# AHRS_Sch.net
KiCad netlist of a schematic drawn in Altium Designer
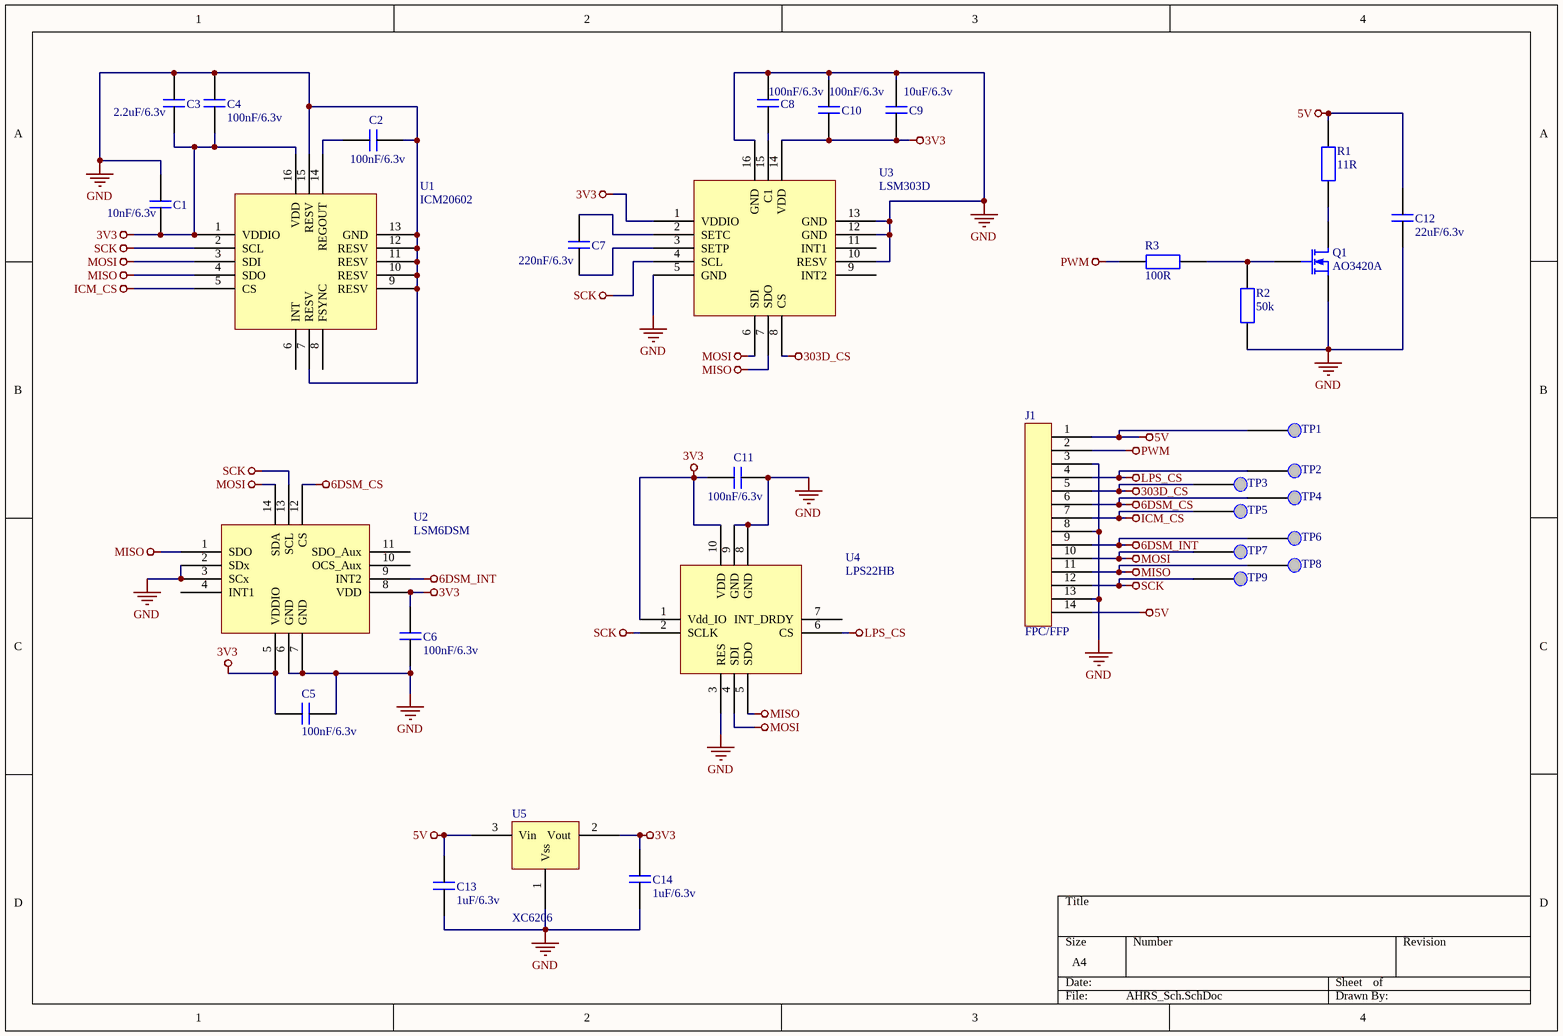
[diagram p0: AHRS_Sch.SchDoc]

(export (version "E")
  (design (tool "Eeschema 10.0.6"))
  (components
    (comp (ref "C1")
      (value "10nF/6.3v")
      (footprint "C_0603")
      (description "Capacitence")
      (libsource (lib "AHRS") (part "Capacitence"))
    )
    (comp (ref "C2")
      (value "100nF/6.3v")
      (footprint "C_0603")
      (description "Capacitence")
      (libsource (lib "AHRS") (part "Capacitence"))
    )
    (comp (ref "C3")
      (value "2.2uF/6.3v")
      (footprint "C_0603")
      (description "Capacitence")
      (libsource (lib "AHRS") (part "Capacitence"))
    )
    (comp (ref "C4")
      (value "100nF/6.3v")
      (footprint "C_0603")
      (description "Capacitence")
      (libsource (lib "AHRS") (part "Capacitence"))
    )
    (comp (ref "C5")
      (value "100nF/6.3v")
      (footprint "C_0603")
      (description "Capacitence")
      (libsource (lib "AHRS") (part "Capacitence"))
    )
    (comp (ref "C6")
      (value "100nF/6.3v")
      (footprint "C_0603")
      (description "Capacitence")
      (libsource (lib "AHRS") (part "Capacitence"))
    )
    (comp (ref "C7")
      (value "220nF/6.3v")
      (footprint "C_0603")
      (description "Capacitence")
      (libsource (lib "AHRS") (part "Capacitence"))
    )
    (comp (ref "C8")
      (value "100nF/6.3v")
      (footprint "C_0603")
      (description "Capacitence")
      (libsource (lib "AHRS") (part "Capacitence"))
    )
    (comp (ref "C9")
      (value "10uF/6.3v")
      (footprint "C_0603")
      (description "Capacitence")
      (libsource (lib "AHRS") (part "Capacitence"))
    )
    (comp (ref "C10")
      (value "100nF/6.3v")
      (footprint "C_0603")
      (description "Capacitence")
      (libsource (lib "AHRS") (part "Capacitence"))
    )
    (comp (ref "C11")
      (value "100nF/6.3v")
      (footprint "C_0603")
      (description "Capacitence")
      (libsource (lib "AHRS") (part "Capacitence"))
    )
    (comp (ref "C12")
      (value "22uF/6.3v")
      (footprint "C_0805")
      (description "Capacitence")
      (libsource (lib "AHRS") (part "Capacitence"))
    )
    (comp (ref "C13")
      (value "1uF/6.3v")
      (footprint "C_0603")
      (description "Capacitence")
      (libsource (lib "AHRS") (part "Capacitence"))
    )
    (comp (ref "C14")
      (value "1uF/6.3v")
      (footprint "C_0603")
      (description "Capacitence")
      (libsource (lib "AHRS") (part "Capacitence"))
    )
    (comp (ref "J1")
      (value "FPC/FFP")
      (footprint "FPC/FFP")
      (description "Connector")
      (libsource (lib "AHRS") (part "FPC/FFP"))
    )
    (comp (ref "Q1")
      (value "AO3420A")
      (footprint "SOT-23")
      (description "MOSFET")
      (libsource (lib "AHRS") (part "AO3420A"))
    )
    (comp (ref "R1")
      (value "11R")
      (footprint "R_2512")
      (description "Resistence")
      (libsource (lib "AHRS") (part "Resistence"))
    )
    (comp (ref "R2")
      (value "50k")
      (footprint "R_0603")
      (description "Resistence")
      (libsource (lib "AHRS") (part "Resistence"))
    )
    (comp (ref "R3")
      (value "100R")
      (footprint "R_0603")
      (description "Resistence")
      (libsource (lib "AHRS") (part "Resistence"))
    )
    (comp (ref "TP1") (value "~") (footprint "Test_Point") (libsource (lib "AHRS") (part "Testpoint")))
    (comp (ref "TP2") (value "~") (footprint "Test_Point") (libsource (lib "AHRS") (part "Testpoint")))
    (comp (ref "TP3") (value "~") (footprint "Test_Point") (libsource (lib "AHRS") (part "Testpoint")))
    (comp (ref "TP4") (value "~") (footprint "Test_Point") (libsource (lib "AHRS") (part "Testpoint")))
    (comp (ref "TP5") (value "~") (footprint "Test_Point") (libsource (lib "AHRS") (part "Testpoint")))
    (comp (ref "TP6") (value "~") (footprint "Test_Point") (libsource (lib "AHRS") (part "Testpoint")))
    (comp (ref "TP7") (value "~") (footprint "Test_Point") (libsource (lib "AHRS") (part "Testpoint")))
    (comp (ref "TP8") (value "~") (footprint "Test_Point") (libsource (lib "AHRS") (part "Testpoint")))
    (comp (ref "TP9") (value "~") (footprint "Test_Point") (libsource (lib "AHRS") (part "Testpoint")))
    (comp (ref "U1")
      (value "ICM20602")
      (footprint "LGA-16")
      (description "IMU")
      (libsource (lib "AHRS") (part "ICM20602"))
    )
    (comp (ref "U2")
      (value "LSM6DSM")
      (footprint "LGA-14L")
      (description "IMU")
      (libsource (lib "AHRS") (part "LSM6DSM"))
    )
    (comp (ref "U3")
      (value "LSM303D")
      (footprint "LGA-16")
      (description "Accelerometer & Compass")
      (libsource (lib "AHRS") (part "LSM303D"))
    )
    (comp (ref "U4")
      (value "LPS22HB")
      (footprint "HLGA-10L")
      (description "Barometer")
      (libsource (lib "AHRS") (part "LPS22HB"))
    )
    (comp (ref "U5")
      (value "XC6206")
      (footprint "SOT-23")
      (description "LDO")
      (libsource (lib "AHRS") (part "XC6206P332"))
    )
  )
  (nets
    (net (code "1") (name "3V3") (class "Default")
      (node (ref "C1") (pin "2") (pinfunction "2_2") (pintype "passive"))
      (node (ref "C10") (pin "1") (pinfunction "1_1") (pintype "passive"))
      (node (ref "C11") (pin "2") (pinfunction "2_2") (pintype "passive"))
      (node (ref "C14") (pin "2") (pinfunction "2_2") (pintype "passive"))
      (node (ref "C3") (pin "2") (pinfunction "2_2") (pintype "passive"))
      (node (ref "C4") (pin "1") (pinfunction "1_1") (pintype "passive"))
      (node (ref "C5") (pin "2") (pinfunction "2_2") (pintype "passive"))
      (node (ref "C6") (pin "2") (pinfunction "2_2") (pintype "passive"))
      (node (ref "C9") (pin "1") (pinfunction "1_1") (pintype "passive"))
      (node (ref "U1") (pin "1") (pinfunction "VDDIO_1") (pintype "passive"))
      (node (ref "U1") (pin "16") (pinfunction "VDD_16") (pintype "passive"))
      (node (ref "U2") (pin "5") (pinfunction "VDDIO_5") (pintype "passive"))
      (node (ref "U2") (pin "8") (pinfunction "VDD_8") (pintype "passive"))
      (node (ref "U3") (pin "1") (pinfunction "VDDIO_1") (pintype "passive"))
      (node (ref "U3") (pin "14") (pinfunction "VDD_14") (pintype "passive"))
      (node (ref "U4") (pin "1") (pinfunction "Vdd_IO_1") (pintype "passive"))
      (node (ref "U4") (pin "10") (pinfunction "VDD_10") (pintype "passive"))
      (node (ref "U5") (pin "2") (pinfunction "Vout_2") (pintype "passive"))
    )
    (net (code "2") (name "5V") (class "Default")
      (node (ref "C12") (pin "2") (pinfunction "2_2") (pintype "passive"))
      (node (ref "C13") (pin "2") (pinfunction "2_2") (pintype "passive"))
      (node (ref "J1") (pin "1") (pintype "passive"))
      (node (ref "J1") (pin "14") (pintype "passive"))
      (node (ref "R1") (pin "1") (pinfunction "1_1") (pintype "passive"))
      (node (ref "TP1") (pin "1") (pinfunction "1_1") (pintype "passive"))
      (node (ref "U5") (pin "3") (pinfunction "Vin_3") (pintype "passive"))
    )
    (net (code "3") (name "6DSM_CS") (class "Default")
      (node (ref "J1") (pin "6") (pintype "passive"))
      (node (ref "TP4") (pin "1") (pinfunction "1_1") (pintype "passive"))
      (node (ref "U2") (pin "12") (pinfunction "CS_12") (pintype "passive"))
    )
    (net (code "4") (name "6DSM_INT") (class "Default")
      (node (ref "J1") (pin "9") (pintype "passive"))
      (node (ref "TP6") (pin "1") (pinfunction "1_1") (pintype "passive"))
      (node (ref "U2") (pin "9") (pinfunction "INT2_9") (pintype "passive"))
    )
    (net (code "5") (name "303D_CS") (class "Default")
      (node (ref "J1") (pin "5") (pintype "passive"))
      (node (ref "TP3") (pin "1") (pinfunction "1_1") (pintype "passive"))
      (node (ref "U3") (pin "8") (pinfunction "CS_8") (pintype "passive"))
    )
    (net (code "6") (name "GND") (class "Default")
      (node (ref "C1") (pin "1") (pinfunction "1_1") (pintype "passive"))
      (node (ref "C10") (pin "2") (pinfunction "2_2") (pintype "passive"))
      (node (ref "C11") (pin "1") (pinfunction "1_1") (pintype "passive"))
      (node (ref "C12") (pin "1") (pinfunction "1_1") (pintype "passive"))
      (node (ref "C13") (pin "1") (pinfunction "1_1") (pintype "passive"))
      (node (ref "C14") (pin "1") (pinfunction "1_1") (pintype "passive"))
      (node (ref "C2") (pin "1") (pinfunction "1_1") (pintype "passive"))
      (node (ref "C3") (pin "1") (pinfunction "1_1") (pintype "passive"))
      (node (ref "C4") (pin "2") (pinfunction "2_2") (pintype "passive"))
      (node (ref "C5") (pin "1") (pinfunction "1_1") (pintype "passive"))
      (node (ref "C6") (pin "1") (pinfunction "1_1") (pintype "passive"))
      (node (ref "C8") (pin "1") (pinfunction "1_1") (pintype "passive"))
      (node (ref "C9") (pin "2") (pinfunction "2_2") (pintype "passive"))
      (node (ref "J1") (pin "13") (pintype "passive"))
      (node (ref "J1") (pin "3") (pintype "passive"))
      (node (ref "J1") (pin "8") (pintype "passive"))
      (node (ref "Q1") (pin "3") (pinfunction "S_3") (pintype "passive"))
      (node (ref "R2") (pin "1") (pinfunction "1_1") (pintype "passive"))
      (node (ref "U1") (pin "10") (pinfunction "RESV_10") (pintype "passive"))
      (node (ref "U1") (pin "11") (pinfunction "RESV_11") (pintype "passive"))
      (node (ref "U1") (pin "12") (pinfunction "RESV_12") (pintype "passive"))
      (node (ref "U1") (pin "13") (pinfunction "GND_13") (pintype "passive"))
      (node (ref "U1") (pin "15") (pinfunction "RESV_15") (pintype "passive"))
      (node (ref "U1") (pin "7") (pinfunction "RESV_7") (pintype "passive"))
      (node (ref "U1") (pin "9") (pinfunction "RESV_9") (pintype "passive"))
      (node (ref "U2") (pin "2") (pinfunction "SDx_2") (pintype "passive"))
      (node (ref "U2") (pin "3") (pinfunction "SCx_3") (pintype "passive"))
      (node (ref "U2") (pin "6") (pinfunction "GND_6") (pintype "passive"))
      (node (ref "U2") (pin "7") (pinfunction "GND_7") (pintype "passive"))
      (node (ref "U3") (pin "10") (pinfunction "RESV_10") (pintype "passive"))
      (node (ref "U3") (pin "12") (pinfunction "GND_12") (pintype "passive"))
      (node (ref "U3") (pin "13") (pinfunction "GND_13") (pintype "passive"))
      (node (ref "U3") (pin "16") (pinfunction "GND_16") (pintype "passive"))
      (node (ref "U3") (pin "5") (pinfunction "GND_5") (pintype "passive"))
      (node (ref "U4") (pin "3") (pinfunction "RES_3") (pintype "passive"))
      (node (ref "U4") (pin "8") (pinfunction "GND_8") (pintype "passive"))
      (node (ref "U4") (pin "9") (pinfunction "GND_9") (pintype "passive"))
      (node (ref "U5") (pin "1") (pinfunction "Vss_1") (pintype "passive"))
    )
    (net (code "7") (name "ICM_CS") (class "Default")
      (node (ref "J1") (pin "7") (pintype "passive"))
      (node (ref "TP5") (pin "1") (pinfunction "1_1") (pintype "passive"))
      (node (ref "U1") (pin "5") (pinfunction "CS_5") (pintype "passive"))
    )
    (net (code "8") (name "LPS_CS") (class "Default")
      (node (ref "J1") (pin "4") (pintype "passive"))
      (node (ref "TP2") (pin "1") (pinfunction "1_1") (pintype "passive"))
      (node (ref "U4") (pin "6") (pinfunction "CS_6") (pintype "passive"))
    )
    (net (code "9") (name "MISO") (class "Default")
      (node (ref "J1") (pin "11") (pintype "passive"))
      (node (ref "TP8") (pin "1") (pinfunction "1_1") (pintype "passive"))
      (node (ref "U1") (pin "4") (pinfunction "SDO_4") (pintype "passive"))
      (node (ref "U2") (pin "1") (pinfunction "SDO_1") (pintype "passive"))
      (node (ref "U3") (pin "7") (pinfunction "SDO_7") (pintype "passive"))
      (node (ref "U4") (pin "5") (pinfunction "SDO_5") (pintype "passive"))
    )
    (net (code "10") (name "MOSI") (class "Default")
      (node (ref "J1") (pin "10") (pintype "passive"))
      (node (ref "TP7") (pin "1") (pinfunction "1_1") (pintype "passive"))
      (node (ref "U1") (pin "3") (pinfunction "SDI_3") (pintype "passive"))
      (node (ref "U2") (pin "14") (pinfunction "SDA_14") (pintype "passive"))
      (node (ref "U3") (pin "6") (pinfunction "SDI_6") (pintype "passive"))
      (node (ref "U4") (pin "4") (pinfunction "SDI_4") (pintype "passive"))
    )
    (net (code "11") (name "Net-(Q1-D)") (class "Default")
      (node (ref "Q1") (pin "2") (pinfunction "D_2") (pintype "passive"))
      (node (ref "R1") (pin "2") (pinfunction "2_2") (pintype "passive"))
    )
    (net (code "12") (name "Net-(Q1-G)") (class "Default")
      (node (ref "Q1") (pin "1") (pinfunction "G_1") (pintype "passive"))
      (node (ref "R2") (pin "2") (pinfunction "2_2") (pintype "passive"))
      (node (ref "R3") (pin "2") (pinfunction "2_2") (pintype "passive"))
    )
    (net (code "13") (name "Net-(U1-REGOUT)") (class "Default")
      (node (ref "C2") (pin "2") (pinfunction "2_2") (pintype "passive"))
      (node (ref "U1") (pin "14") (pinfunction "REGOUT_14") (pintype "passive"))
    )
    (net (code "14") (name "Net-(U3-C1)") (class "Default")
      (node (ref "C8") (pin "2") (pinfunction "2_2") (pintype "passive"))
      (node (ref "U3") (pin "15") (pinfunction "C1_15") (pintype "passive"))
    )
    (net (code "15") (name "Net-(U3-SETC)") (class "Default")
      (node (ref "C7") (pin "1") (pinfunction "1_1") (pintype "passive"))
      (node (ref "U3") (pin "2") (pinfunction "SETC_2") (pintype "passive"))
    )
    (net (code "16") (name "Net-(U3-SETP)") (class "Default")
      (node (ref "C7") (pin "2") (pinfunction "2_2") (pintype "passive"))
      (node (ref "U3") (pin "3") (pinfunction "SETP_3") (pintype "passive"))
    )
    (net (code "17") (name "PWM") (class "Default")
      (node (ref "J1") (pin "2") (pintype "passive"))
      (node (ref "R3") (pin "1") (pinfunction "1_1") (pintype "passive"))
    )
    (net (code "18") (name "SCK") (class "Default")
      (node (ref "J1") (pin "12") (pintype "passive"))
      (node (ref "TP9") (pin "1") (pinfunction "1_1") (pintype "passive"))
      (node (ref "U1") (pin "2") (pinfunction "SCL_2") (pintype "passive"))
      (node (ref "U2") (pin "13") (pinfunction "SCL_13") (pintype "passive"))
      (node (ref "U3") (pin "4") (pinfunction "SCL_4") (pintype "passive"))
      (node (ref "U4") (pin "2") (pinfunction "SCLK_2") (pintype "passive"))
    )
    (net (code "19") (name "unconnected-(U1-FSYNC-Pad8)") (class "Default")
      (node (ref "U1") (pin "8") (pinfunction "FSYNC_8") (pintype "passive"))
    )
    (net (code "20") (name "unconnected-(U1-INT-Pad6)") (class "Default")
      (node (ref "U1") (pin "6") (pinfunction "INT_6") (pintype "passive"))
    )
    (net (code "21") (name "unconnected-(U2-INT1-Pad4)") (class "Default")
      (node (ref "U2") (pin "4") (pinfunction "INT1_4") (pintype "passive"))
    )
    (net (code "22") (name "unconnected-(U2-OCS_Aux-Pad10)") (class "Default")
      (node (ref "U2") (pin "10") (pinfunction "OCS_Aux_10") (pintype "passive"))
    )
    (net (code "23") (name "unconnected-(U2-SDO_Aux-Pad11)") (class "Default")
      (node (ref "U2") (pin "11") (pinfunction "SDO_Aux_11") (pintype "passive"))
    )
    (net (code "24") (name "unconnected-(U3-INT1-Pad11)") (class "Default")
      (node (ref "U3") (pin "11") (pinfunction "INT1_11") (pintype "passive"))
    )
    (net (code "25") (name "unconnected-(U3-INT2-Pad9)") (class "Default")
      (node (ref "U3") (pin "9") (pinfunction "INT2_9") (pintype "passive"))
    )
    (net (code "26") (name "unconnected-(U4-INT_DRDY-Pad7)") (class "Default")
      (node (ref "U4") (pin "7") (pinfunction "INT_DRDY_7") (pintype "passive"))
    )
  )
)
